# Mis_-_Voltage_Regulators_500m_SMD.net
KiCad netlist of a schematic drawn in Altium Designer
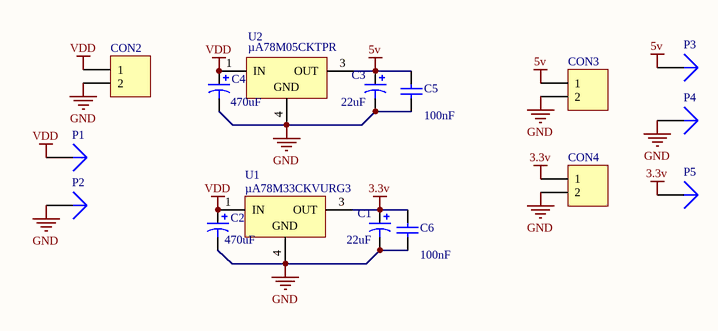
[diagram p0: Mis - Voltage Regulators 500m SMD.SchDoc]

(export (version "E")
  (design (tool "Eeschema 10.0.6"))
  (components
    (comp (ref "C1")
      (value "22uF")
      (footprint "C-4x4")
      (description "Polarized Capacitor (Axial)")
      (fields (field (name "Comment") "Cap Pol2") (field (name "PUBLISHER") "Altium Limited"))
      (libsource (lib "Miscellaneous Devices") (part "Cap Pol2"))
    )
    (comp (ref "C2")
      (value "470uF")
      (footprint "C-10x10")
      (description "Polarized Capacitor (Axial)")
      (fields (field (name "Comment") "Cap Pol2") (field (name "PUBLISHER") "Altium Limited"))
      (libsource (lib "Miscellaneous Devices") (part "Cap Pol2"))
    )
    (comp (ref "C3")
      (value "22uF")
      (footprint "C-4x4")
      (description "Polarized Capacitor (Axial)")
      (fields (field (name "Comment") "Cap Pol2") (field (name "PUBLISHER") "Altium Limited"))
      (libsource (lib "Miscellaneous Devices") (part "Cap Pol2"))
    )
    (comp (ref "C4")
      (value "470uF")
      (footprint "C-10x10")
      (description "Polarized Capacitor (Axial)")
      (fields (field (name "Comment") "Cap Pol2") (field (name "PUBLISHER") "Altium Limited"))
      (libsource (lib "Miscellaneous Devices") (part "Cap Pol2"))
    )
    (comp (ref "C5")
      (value "100nF")
      (footprint "4532[1812]")
      (description "Capacitor")
      (fields (field (name "Comment") "Cap") (field (name "PUBLISHER") "Altium Limited"))
      (libsource (lib "Miscellaneous Devices") (part "Cap"))
    )
    (comp (ref "C6")
      (value "100nF")
      (footprint "4532[1812]")
      (description "Capacitor")
      (fields (field (name "Comment") "Cap") (field (name "PUBLISHER") "Altium Limited"))
      (libsource (lib "Miscellaneous Devices") (part "Cap"))
    )
    (comp (ref "CON2")
      (value "Header 2")
      (footprint "HDR1X2")
      (description "Header, 2-Pin")
      (fields (field (name "PUBLISHER") "Altium Limited"))
      (libsource (lib "Miscellaneous Connectors") (part "Header 2"))
    )
    (comp (ref "CON3")
      (value "Header 2")
      (footprint "HDR1X2")
      (description "Header, 2-Pin")
      (fields (field (name "PUBLISHER") "Altium Limited"))
      (libsource (lib "Miscellaneous Connectors") (part "Header 2"))
    )
    (comp (ref "CON4")
      (value "Header 2")
      (footprint "HDR1X2")
      (description "Header, 2-Pin")
      (fields (field (name "PUBLISHER") "Altium Limited"))
      (libsource (lib "Miscellaneous Connectors") (part "Header 2"))
    )
    (comp (ref "P1")
      (value "Plug")
      (footprint "PIN1")
      (fields (field (name "PUBLISHER") "Altium Limited"))
      (libsource (lib "Miscellaneous Connectors") (part "Plug"))
    )
    (comp (ref "P2")
      (value "Plug")
      (footprint "PIN1")
      (fields (field (name "PUBLISHER") "Altium Limited"))
      (libsource (lib "Miscellaneous Connectors") (part "Plug"))
    )
    (comp (ref "P3")
      (value "Plug")
      (footprint "PIN1")
      (fields (field (name "PUBLISHER") "Altium Limited"))
      (libsource (lib "Miscellaneous Connectors") (part "Plug"))
    )
    (comp (ref "P4")
      (value "Plug")
      (footprint "PIN1")
      (fields (field (name "PUBLISHER") "Altium Limited"))
      (libsource (lib "Miscellaneous Connectors") (part "Plug"))
    )
    (comp (ref "P5")
      (value "Plug")
      (footprint "PIN1")
      (fields (field (name "PUBLISHER") "Altium Limited"))
      (libsource (lib "Miscellaneous Connectors") (part "Plug"))
    )
    (comp (ref "U1")
      (value "µA78M33CKVURG3")
      (footprint "KTP02")
      (description "Positive-Voltage Regulator")
      (libsource (lib "TI Power Mgt Voltage Regulator") (part "µA78M33CKVURG3"))
    )
    (comp (ref "U2")
      (value "µA78M05CKTPR")
      (footprint "KTP02")
      (description "Positive-Voltage Regulator")
      (fields (field (name "PUBLISHER") "Altium Limited"))
      (libsource (lib "TI Power Mgt Voltage Regulator") (part "µA78M05CKTPR"))
    )
  )
  (nets
    (net (code "1") (name "3.3v") (class "Default")
      (node (ref "C1") (pin "1") (pinfunction "1_1") (pintype "passive"))
      (node (ref "C6") (pin "2") (pinfunction "2_2") (pintype "passive"))
      (node (ref "CON4") (pin "1") (pinfunction "1_1") (pintype "passive"))
      (node (ref "P5") (pin "1") (pinfunction "1_1") (pintype "passive"))
      (node (ref "U1") (pin "3") (pinfunction "OUT_3") (pintype "power_in"))
    )
    (net (code "2") (name "5v") (class "Default")
      (node (ref "C3") (pin "1") (pinfunction "1_1") (pintype "passive"))
      (node (ref "C5") (pin "2") (pinfunction "2_2") (pintype "passive"))
      (node (ref "CON3") (pin "1") (pinfunction "1_1") (pintype "passive"))
      (node (ref "P3") (pin "1") (pinfunction "1_1") (pintype "passive"))
      (node (ref "U2") (pin "3") (pinfunction "OUT_3") (pintype "power_in"))
    )
    (net (code "3") (name "GND") (class "Default")
      (node (ref "C1") (pin "2") (pinfunction "2_2") (pintype "passive"))
      (node (ref "C2") (pin "2") (pinfunction "2_2") (pintype "passive"))
      (node (ref "C3") (pin "2") (pinfunction "2_2") (pintype "passive"))
      (node (ref "C4") (pin "2") (pinfunction "2_2") (pintype "passive"))
      (node (ref "C5") (pin "1") (pinfunction "1_1") (pintype "passive"))
      (node (ref "C6") (pin "1") (pinfunction "1_1") (pintype "passive"))
      (node (ref "CON2") (pin "2") (pinfunction "2_2") (pintype "passive"))
      (node (ref "CON3") (pin "2") (pinfunction "2_2") (pintype "passive"))
      (node (ref "CON4") (pin "2") (pinfunction "2_2") (pintype "passive"))
      (node (ref "P2") (pin "1") (pinfunction "1_1") (pintype "passive"))
      (node (ref "P4") (pin "1") (pinfunction "1_1") (pintype "passive"))
      (node (ref "U1") (pin "4") (pinfunction "GND_4") (pintype "power_in"))
      (node (ref "U2") (pin "4") (pinfunction "GND_4") (pintype "power_in"))
    )
    (net (code "4") (name "VDD") (class "Default")
      (node (ref "C2") (pin "1") (pinfunction "1_1") (pintype "passive"))
      (node (ref "C4") (pin "1") (pinfunction "1_1") (pintype "passive"))
      (node (ref "CON2") (pin "1") (pinfunction "1_1") (pintype "passive"))
      (node (ref "P1") (pin "1") (pinfunction "1_1") (pintype "passive"))
      (node (ref "U1") (pin "1") (pinfunction "IN_1") (pintype "power_in"))
      (node (ref "U2") (pin "1") (pinfunction "IN_1") (pintype "power_in"))
    )
  )
)
